# Dir_Control.net
KiCad netlist of a schematic drawn in Altium Designer
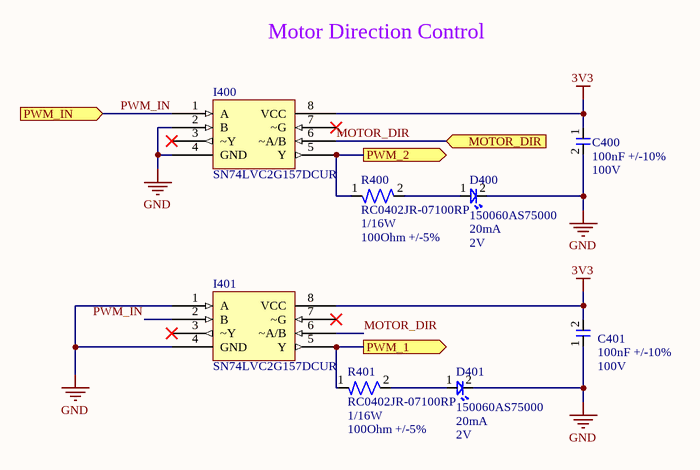
[diagram p0: Dir_Control.SchDoc]

(export (version "E")
  (design (tool "Eeschema 10.0.6"))
  (components
    (comp (ref "C400")
      (value "CC0603KRX7R0BB104")
      (footprint "MasterLib:CAP-0603")
      (description "CAP CER 0.1UF 100V X7R 0603")
      (fields
        (field (name "MANUFACTURER") "YAGEO")
        (field (name "CAPACITANCE") "100nF +/-10%")
        (field (name "VOLTAGE RATING") "100V")
      )
      (libsource (lib "MasterLib") (part "CAP-100N-0001"))
    )
    (comp (ref "C401")
      (value "CC0603KRX7R0BB104")
      (footprint "MasterLib:CAP-0603")
      (description "CAP CER 0.1UF 100V X7R 0603")
      (fields
        (field (name "MANUFACTURER") "YAGEO")
        (field (name "CAPACITANCE") "100nF +/-10%")
        (field (name "VOLTAGE RATING") "100V")
      )
      (libsource (lib "MasterLib") (part "CAP-100N-0001"))
    )
    (comp (ref "D400")
      (value "150060AS75000")
      (footprint "MasterLib:LED-0603")
      (description "CAP CER 0.1UF 100V X7R 0603")
      (fields
        (field (name "MANUFACTURER") "Wurth Electronik")
        (field (name "CURRENT RATING") "20mA")
        (field (name "VF") "2V")
      )
      (libsource (lib "MasterLib") (part "LED_Amber_0001"))
    )
    (comp (ref "D401")
      (value "150060AS75000")
      (footprint "MasterLib:LED-0603")
      (description "CAP CER 0.1UF 100V X7R 0603")
      (fields
        (field (name "MANUFACTURER") "Wurth Electronik")
        (field (name "CURRENT RATING") "20mA")
        (field (name "VF") "2V")
      )
      (libsource (lib "MasterLib") (part "LED_Amber_0001"))
    )
    (comp (ref "I400")
      (value "SN74LVC2G157DCUR")
      (footprint "MasterLib:IC-MUX-8VSSOP")
      (libsource (lib "MasterLib") (part "IC-MUX-0001"))
    )
    (comp (ref "I401")
      (value "SN74LVC2G157DCUR")
      (footprint "MasterLib:IC-MUX-8VSSOP")
      (description "Multiplexer 1 x 2:1 8-VSSOP")
      (libsource (lib "MasterLib") (part "IC-MUX-0001"))
    )
    (comp (ref "R400")
      (value "RC0402JR-07100RP")
      (footprint "MasterLib:RES-0402")
      (description "RES SMD 100 OHM 5% 1/16W 0402")
      (fields
        (field (name "MANUFACTURER") "YAGEO")
        (field (name "POWER RATING") "1/16W")
        (field (name "RESISTANCE") "100Ohm +/-5%")
      )
      (libsource (lib "MasterLib") (part "RES-100-0001"))
    )
    (comp (ref "R401")
      (value "RC0402JR-07100RP")
      (footprint "MasterLib:RES-0402")
      (description "RES SMD 100 OHM 5% 1/16W 0402")
      (fields
        (field (name "MANUFACTURER") "YAGEO")
        (field (name "POWER RATING") "1/16W")
        (field (name "RESISTANCE") "100Ohm +/-5%")
      )
      (libsource (lib "MasterLib") (part "RES-100-0001"))
    )
  )
  (nets
    (net (code "1") (name "/MOTOR_DIR") (class "Default")
      (node (ref "I400") (pin "6") (pinfunction "~A/B_6") (pintype "input"))
      (node (ref "I401") (pin "6") (pinfunction "~A/B_6") (pintype "input"))
    )
    (net (code "2") (name "/PWM_1") (class "Default")
      (node (ref "I401") (pin "5") (pinfunction "Y_5") (pintype "output"))
      (node (ref "R401") (pin "1") (pinfunction "1_1") (pintype "passive"))
    )
    (net (code "3") (name "/PWM_2") (class "Default")
      (node (ref "I400") (pin "5") (pinfunction "Y_5") (pintype "output"))
      (node (ref "R400") (pin "1") (pinfunction "1_1") (pintype "passive"))
    )
    (net (code "4") (name "/PWM_IN") (class "Default")
      (node (ref "I400") (pin "1") (pinfunction "A_1") (pintype "input"))
      (node (ref "I401") (pin "2") (pinfunction "B_2") (pintype "input"))
    )
    (net (code "5") (name "3V3") (class "Default")
      (node (ref "C400") (pin "1") (pinfunction "1_1") (pintype "passive"))
      (node (ref "C401") (pin "2") (pinfunction "2_2") (pintype "passive"))
      (node (ref "I400") (pin "8") (pinfunction "VCC_8") (pintype "power_in"))
      (node (ref "I401") (pin "8") (pinfunction "VCC_8") (pintype "power_in"))
    )
    (net (code "6") (name "GND") (class "Default")
      (node (ref "C400") (pin "2") (pinfunction "2_2") (pintype "passive"))
      (node (ref "C401") (pin "1") (pinfunction "1_1") (pintype "passive"))
      (node (ref "D400") (pin "2") (pinfunction "2_2") (pintype "passive"))
      (node (ref "D401") (pin "2") (pinfunction "2_2") (pintype "passive"))
      (node (ref "I400") (pin "2") (pinfunction "B_2") (pintype "input"))
      (node (ref "I400") (pin "4") (pinfunction "GND_4") (pintype "power_in"))
      (node (ref "I401") (pin "1") (pinfunction "A_1") (pintype "input"))
      (node (ref "I401") (pin "4") (pinfunction "GND_4") (pintype "power_in"))
    )
    (net (code "7") (name "Net-(D400-Pad1)") (class "Default")
      (node (ref "D400") (pin "1") (pinfunction "1_1") (pintype "passive"))
      (node (ref "R400") (pin "2") (pinfunction "2_2") (pintype "passive"))
    )
    (net (code "8") (name "Net-(D401-Pad1)") (class "Default")
      (node (ref "D401") (pin "1") (pinfunction "1_1") (pintype "passive"))
      (node (ref "R401") (pin "2") (pinfunction "2_2") (pintype "passive"))
    )
    (net (code "9") (name "unconnected-(I400-~G-Pad7)") (class "Default")
      (node (ref "I400") (pin "7") (pinfunction "~G_7") (pintype "input+no_connect"))
    )
    (net (code "10") (name "unconnected-(I400-~Y-Pad3)") (class "Default")
      (node (ref "I400") (pin "3") (pinfunction "~Y_3") (pintype "output+no_connect"))
    )
    (net (code "11") (name "unconnected-(I401-~G-Pad7)") (class "Default")
      (node (ref "I401") (pin "7") (pinfunction "~G_7") (pintype "input+no_connect"))
    )
    (net (code "12") (name "unconnected-(I401-~Y-Pad3)") (class "Default")
      (node (ref "I401") (pin "3") (pinfunction "~Y_3") (pintype "output+no_connect"))
    )
  )
)
